# Main.net
KiCad netlist of a schematic drawn in Altium Designer
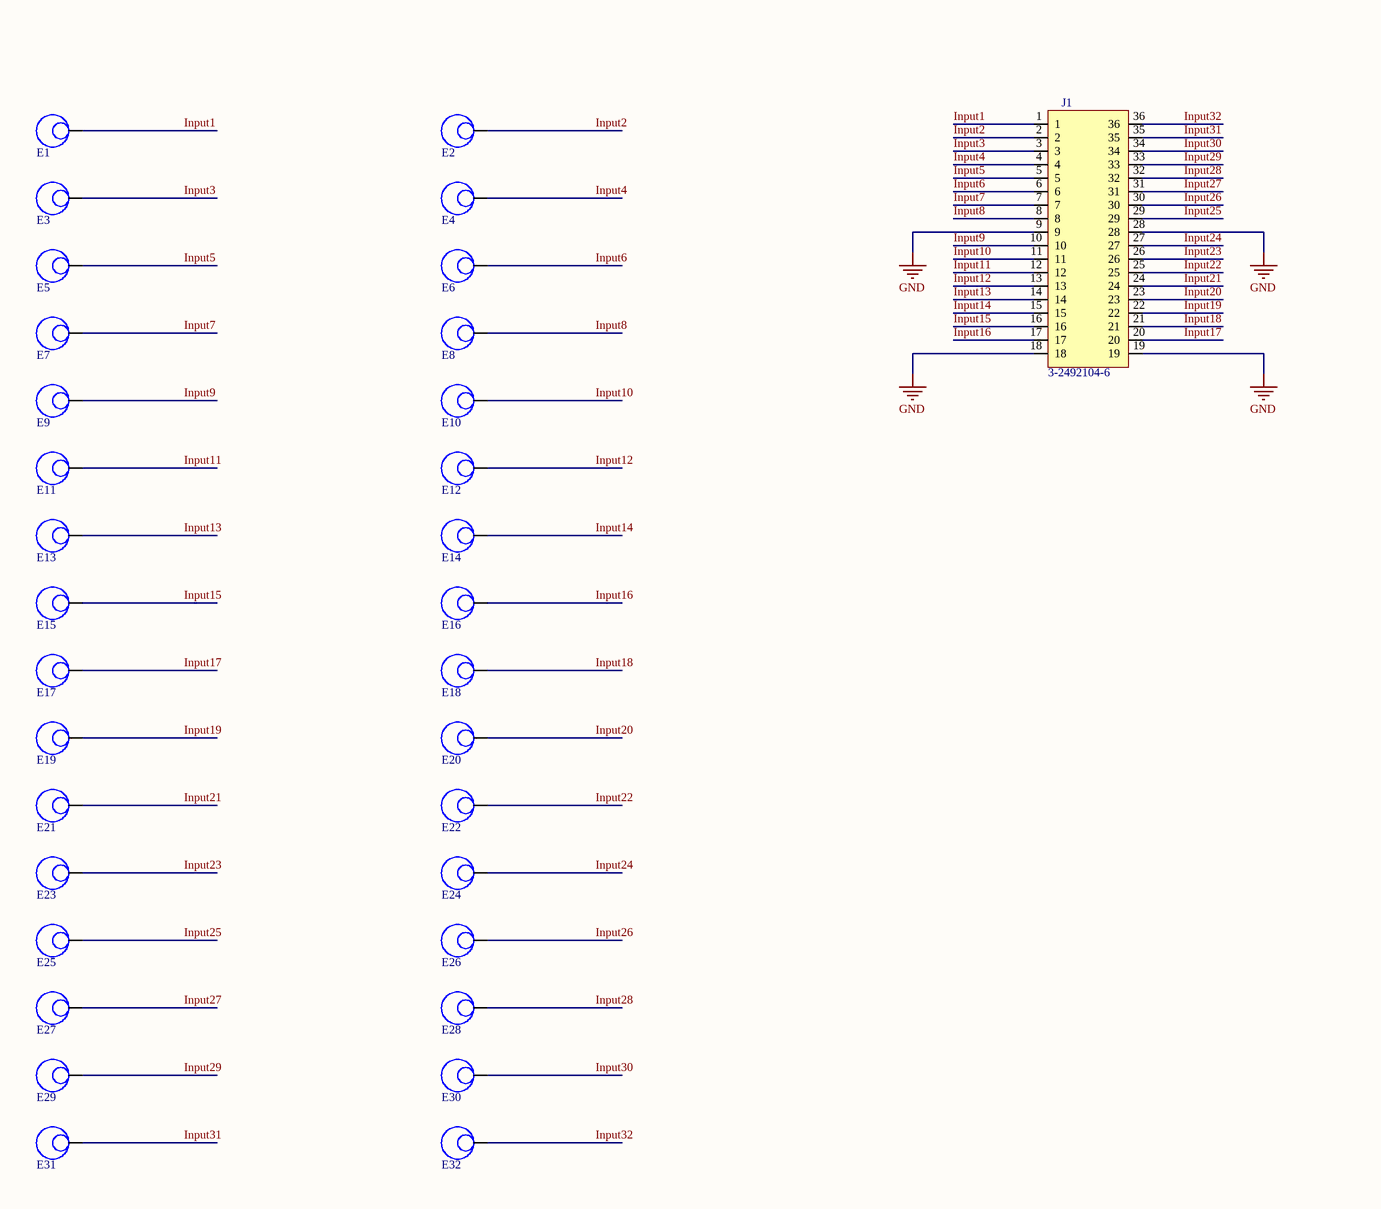
[diagram p0: Main.SchDoc, left]
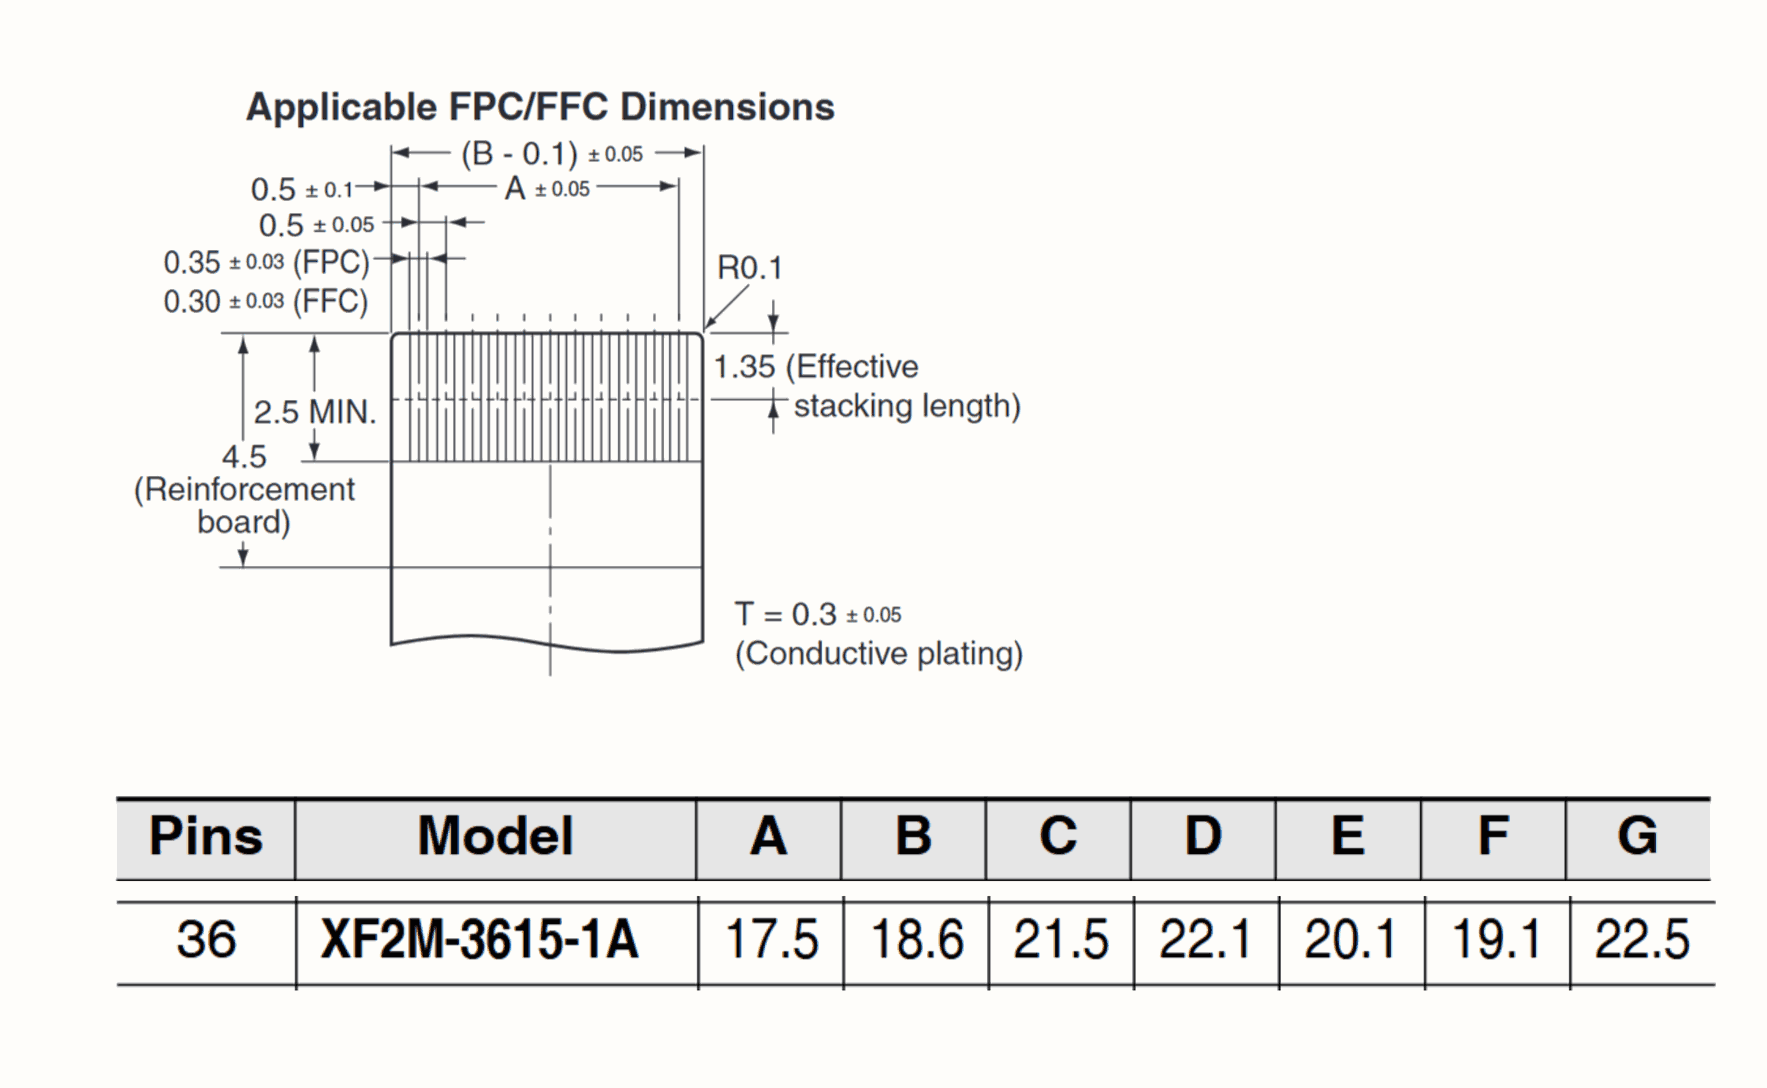
[diagram p1: Main.SchDoc, right]

(export (version "E")
  (design (tool "Eeschema 10.0.6"))
  (components
    (comp (ref "E1")
      (value "UNeedle")
      (footprint "UNeedle")
      (libsource (lib "Microneedle_Lib") (part "UNeedle"))
    )
    (comp (ref "E2")
      (value "UNeedle")
      (footprint "UNeedle")
      (libsource (lib "Microneedle_Lib") (part "UNeedle"))
    )
    (comp (ref "E3")
      (value "UNeedle")
      (footprint "UNeedle")
      (libsource (lib "Microneedle_Lib") (part "UNeedle"))
    )
    (comp (ref "E4")
      (value "UNeedle")
      (footprint "UNeedle")
      (libsource (lib "Microneedle_Lib") (part "UNeedle"))
    )
    (comp (ref "E5")
      (value "UNeedle")
      (footprint "UNeedle")
      (libsource (lib "Microneedle_Lib") (part "UNeedle"))
    )
    (comp (ref "E6")
      (value "UNeedle")
      (footprint "UNeedle")
      (libsource (lib "Microneedle_Lib") (part "UNeedle"))
    )
    (comp (ref "E7")
      (value "UNeedle")
      (footprint "UNeedle")
      (libsource (lib "Microneedle_Lib") (part "UNeedle"))
    )
    (comp (ref "E8")
      (value "UNeedle")
      (footprint "UNeedle")
      (libsource (lib "Microneedle_Lib") (part "UNeedle"))
    )
    (comp (ref "E9")
      (value "UNeedle")
      (footprint "UNeedle")
      (libsource (lib "Microneedle_Lib") (part "UNeedle"))
    )
    (comp (ref "E10")
      (value "UNeedle")
      (footprint "UNeedle")
      (libsource (lib "Microneedle_Lib") (part "UNeedle"))
    )
    (comp (ref "E11")
      (value "UNeedle")
      (footprint "UNeedle")
      (libsource (lib "Microneedle_Lib") (part "UNeedle"))
    )
    (comp (ref "E12")
      (value "UNeedle")
      (footprint "UNeedle")
      (libsource (lib "Microneedle_Lib") (part "UNeedle"))
    )
    (comp (ref "E13")
      (value "UNeedle")
      (footprint "UNeedle")
      (libsource (lib "Microneedle_Lib") (part "UNeedle"))
    )
    (comp (ref "E14")
      (value "UNeedle")
      (footprint "UNeedle")
      (libsource (lib "Microneedle_Lib") (part "UNeedle"))
    )
    (comp (ref "E15")
      (value "UNeedle")
      (footprint "UNeedle")
      (libsource (lib "Microneedle_Lib") (part "UNeedle"))
    )
    (comp (ref "E16")
      (value "UNeedle")
      (footprint "UNeedle")
      (libsource (lib "Microneedle_Lib") (part "UNeedle"))
    )
    (comp (ref "E17")
      (value "UNeedle")
      (footprint "UNeedle")
      (libsource (lib "Microneedle_Lib") (part "UNeedle"))
    )
    (comp (ref "E18")
      (value "UNeedle")
      (footprint "UNeedle")
      (libsource (lib "Microneedle_Lib") (part "UNeedle"))
    )
    (comp (ref "E19")
      (value "UNeedle")
      (footprint "UNeedle")
      (libsource (lib "Microneedle_Lib") (part "UNeedle"))
    )
    (comp (ref "E20")
      (value "UNeedle")
      (footprint "UNeedle")
      (libsource (lib "Microneedle_Lib") (part "UNeedle"))
    )
    (comp (ref "E21")
      (value "UNeedle")
      (footprint "UNeedle")
      (libsource (lib "Microneedle_Lib") (part "UNeedle"))
    )
    (comp (ref "E22")
      (value "UNeedle")
      (footprint "UNeedle")
      (libsource (lib "Microneedle_Lib") (part "UNeedle"))
    )
    (comp (ref "E23")
      (value "UNeedle")
      (footprint "UNeedle")
      (libsource (lib "Microneedle_Lib") (part "UNeedle"))
    )
    (comp (ref "E24")
      (value "UNeedle")
      (footprint "UNeedle")
      (libsource (lib "Microneedle_Lib") (part "UNeedle"))
    )
    (comp (ref "E25")
      (value "UNeedle")
      (footprint "UNeedle")
      (libsource (lib "Microneedle_Lib") (part "UNeedle"))
    )
    (comp (ref "E26")
      (value "UNeedle")
      (footprint "UNeedle")
      (libsource (lib "Microneedle_Lib") (part "UNeedle"))
    )
    (comp (ref "E27")
      (value "UNeedle")
      (footprint "UNeedle")
      (libsource (lib "Microneedle_Lib") (part "UNeedle"))
    )
    (comp (ref "E28")
      (value "UNeedle")
      (footprint "UNeedle")
      (libsource (lib "Microneedle_Lib") (part "UNeedle"))
    )
    (comp (ref "E29")
      (value "UNeedle")
      (footprint "UNeedle")
      (libsource (lib "Microneedle_Lib") (part "UNeedle"))
    )
    (comp (ref "E30")
      (value "UNeedle")
      (footprint "UNeedle")
      (libsource (lib "Microneedle_Lib") (part "UNeedle"))
    )
    (comp (ref "E31")
      (value "UNeedle")
      (footprint "UNeedle")
      (libsource (lib "Microneedle_Lib") (part "UNeedle"))
    )
    (comp (ref "E32")
      (value "UNeedle")
      (footprint "UNeedle")
      (libsource (lib "Microneedle_Lib") (part "UNeedle"))
    )
    (comp (ref "J1")
      (value "3-2492104-6")
      (footprint "Fingers")
      (description "XXX - Description - Package")
      (libsource (lib "Microneedle_Lib") (part "Fingers"))
    )
  )
  (nets
    (net (code "1") (name "/Input1") (class "Default")
      (node (ref "E1") (pin "1") (pinfunction "1_1") (pintype "passive"))
      (node (ref "J1") (pin "1") (pinfunction "1_1") (pintype "passive"))
    )
    (net (code "2") (name "/Input2") (class "Default")
      (node (ref "E2") (pin "1") (pinfunction "1_1") (pintype "passive"))
      (node (ref "J1") (pin "2") (pinfunction "2_2") (pintype "passive"))
    )
    (net (code "3") (name "/Input3") (class "Default")
      (node (ref "E3") (pin "1") (pinfunction "1_1") (pintype "passive"))
      (node (ref "J1") (pin "3") (pinfunction "3_3") (pintype "passive"))
    )
    (net (code "4") (name "/Input4") (class "Default")
      (node (ref "E4") (pin "1") (pinfunction "1_1") (pintype "passive"))
      (node (ref "J1") (pin "4") (pinfunction "4_4") (pintype "passive"))
    )
    (net (code "5") (name "/Input5") (class "Default")
      (node (ref "E5") (pin "1") (pinfunction "1_1") (pintype "passive"))
      (node (ref "J1") (pin "5") (pinfunction "5_5") (pintype "passive"))
    )
    (net (code "6") (name "/Input6") (class "Default")
      (node (ref "E6") (pin "1") (pinfunction "1_1") (pintype "passive"))
      (node (ref "J1") (pin "6") (pinfunction "6_6") (pintype "passive"))
    )
    (net (code "7") (name "/Input7") (class "Default")
      (node (ref "E7") (pin "1") (pinfunction "1_1") (pintype "passive"))
      (node (ref "J1") (pin "7") (pinfunction "7_7") (pintype "passive"))
    )
    (net (code "8") (name "/Input8") (class "Default")
      (node (ref "E8") (pin "1") (pinfunction "1_1") (pintype "passive"))
      (node (ref "J1") (pin "8") (pinfunction "8_8") (pintype "passive"))
    )
    (net (code "9") (name "/Input9") (class "Default")
      (node (ref "E9") (pin "1") (pinfunction "1_1") (pintype "passive"))
      (node (ref "J1") (pin "10") (pinfunction "10_10") (pintype "passive"))
    )
    (net (code "10") (name "/Input10") (class "Default")
      (node (ref "E10") (pin "1") (pinfunction "1_1") (pintype "passive"))
      (node (ref "J1") (pin "11") (pinfunction "11_11") (pintype "passive"))
    )
    (net (code "11") (name "/Input11") (class "Default")
      (node (ref "E11") (pin "1") (pinfunction "1_1") (pintype "passive"))
      (node (ref "J1") (pin "12") (pinfunction "12_12") (pintype "passive"))
    )
    (net (code "12") (name "/Input12") (class "Default")
      (node (ref "E12") (pin "1") (pinfunction "1_1") (pintype "passive"))
      (node (ref "J1") (pin "13") (pinfunction "13_13") (pintype "passive"))
    )
    (net (code "13") (name "/Input13") (class "Default")
      (node (ref "E13") (pin "1") (pinfunction "1_1") (pintype "passive"))
      (node (ref "J1") (pin "14") (pinfunction "14_14") (pintype "passive"))
    )
    (net (code "14") (name "/Input14") (class "Default")
      (node (ref "E14") (pin "1") (pinfunction "1_1") (pintype "passive"))
      (node (ref "J1") (pin "15") (pinfunction "15_15") (pintype "passive"))
    )
    (net (code "15") (name "/Input15") (class "Default")
      (node (ref "E15") (pin "1") (pinfunction "1_1") (pintype "passive"))
      (node (ref "J1") (pin "16") (pinfunction "16_16") (pintype "passive"))
    )
    (net (code "16") (name "/Input16") (class "Default")
      (node (ref "E16") (pin "1") (pinfunction "1_1") (pintype "passive"))
      (node (ref "J1") (pin "17") (pinfunction "17_17") (pintype "passive"))
    )
    (net (code "17") (name "/Input17") (class "Default")
      (node (ref "E17") (pin "1") (pinfunction "1_1") (pintype "passive"))
      (node (ref "J1") (pin "20") (pinfunction "20_20") (pintype "passive"))
    )
    (net (code "18") (name "/Input18") (class "Default")
      (node (ref "E18") (pin "1") (pinfunction "1_1") (pintype "passive"))
      (node (ref "J1") (pin "21") (pinfunction "21_21") (pintype "passive"))
    )
    (net (code "19") (name "/Input19") (class "Default")
      (node (ref "E19") (pin "1") (pinfunction "1_1") (pintype "passive"))
      (node (ref "J1") (pin "22") (pinfunction "22_22") (pintype "passive"))
    )
    (net (code "20") (name "/Input20") (class "Default")
      (node (ref "E20") (pin "1") (pinfunction "1_1") (pintype "passive"))
      (node (ref "J1") (pin "23") (pinfunction "23_23") (pintype "passive"))
    )
    (net (code "21") (name "/Input21") (class "Default")
      (node (ref "E21") (pin "1") (pinfunction "1_1") (pintype "passive"))
      (node (ref "J1") (pin "24") (pinfunction "24_24") (pintype "passive"))
    )
    (net (code "22") (name "/Input22") (class "Default")
      (node (ref "E22") (pin "1") (pinfunction "1_1") (pintype "passive"))
      (node (ref "J1") (pin "25") (pinfunction "25_25") (pintype "passive"))
    )
    (net (code "23") (name "/Input23") (class "Default")
      (node (ref "E23") (pin "1") (pinfunction "1_1") (pintype "passive"))
      (node (ref "J1") (pin "26") (pinfunction "26_26") (pintype "passive"))
    )
    (net (code "24") (name "/Input24") (class "Default")
      (node (ref "E24") (pin "1") (pinfunction "1_1") (pintype "passive"))
      (node (ref "J1") (pin "27") (pinfunction "27_27") (pintype "passive"))
    )
    (net (code "25") (name "/Input25") (class "Default")
      (node (ref "E25") (pin "1") (pinfunction "1_1") (pintype "passive"))
      (node (ref "J1") (pin "29") (pinfunction "29_29") (pintype "passive"))
    )
    (net (code "26") (name "/Input26") (class "Default")
      (node (ref "E26") (pin "1") (pinfunction "1_1") (pintype "passive"))
      (node (ref "J1") (pin "30") (pinfunction "30_30") (pintype "passive"))
    )
    (net (code "27") (name "/Input27") (class "Default")
      (node (ref "E27") (pin "1") (pinfunction "1_1") (pintype "passive"))
      (node (ref "J1") (pin "31") (pinfunction "31_31") (pintype "passive"))
    )
    (net (code "28") (name "/Input28") (class "Default")
      (node (ref "E28") (pin "1") (pinfunction "1_1") (pintype "passive"))
      (node (ref "J1") (pin "32") (pinfunction "32_32") (pintype "passive"))
    )
    (net (code "29") (name "/Input29") (class "Default")
      (node (ref "E29") (pin "1") (pinfunction "1_1") (pintype "passive"))
      (node (ref "J1") (pin "33") (pinfunction "33_33") (pintype "passive"))
    )
    (net (code "30") (name "/Input30") (class "Default")
      (node (ref "E30") (pin "1") (pinfunction "1_1") (pintype "passive"))
      (node (ref "J1") (pin "34") (pinfunction "34_34") (pintype "passive"))
    )
    (net (code "31") (name "/Input31") (class "Default")
      (node (ref "E31") (pin "1") (pinfunction "1_1") (pintype "passive"))
      (node (ref "J1") (pin "35") (pinfunction "35_35") (pintype "passive"))
    )
    (net (code "32") (name "/Input32") (class "Default")
      (node (ref "E32") (pin "1") (pinfunction "1_1") (pintype "passive"))
      (node (ref "J1") (pin "36") (pinfunction "36_36") (pintype "passive"))
    )
    (net (code "33") (name "GND") (class "Default")
      (node (ref "J1") (pin "18") (pinfunction "18_18") (pintype "passive"))
      (node (ref "J1") (pin "19") (pinfunction "19_19") (pintype "passive"))
      (node (ref "J1") (pin "28") (pinfunction "28_28") (pintype "passive"))
      (node (ref "J1") (pin "9") (pinfunction "9_9") (pintype "passive"))
    )
  )
)
